# DroidOS.net
KiCad netlist of a schematic drawn in EAGLE
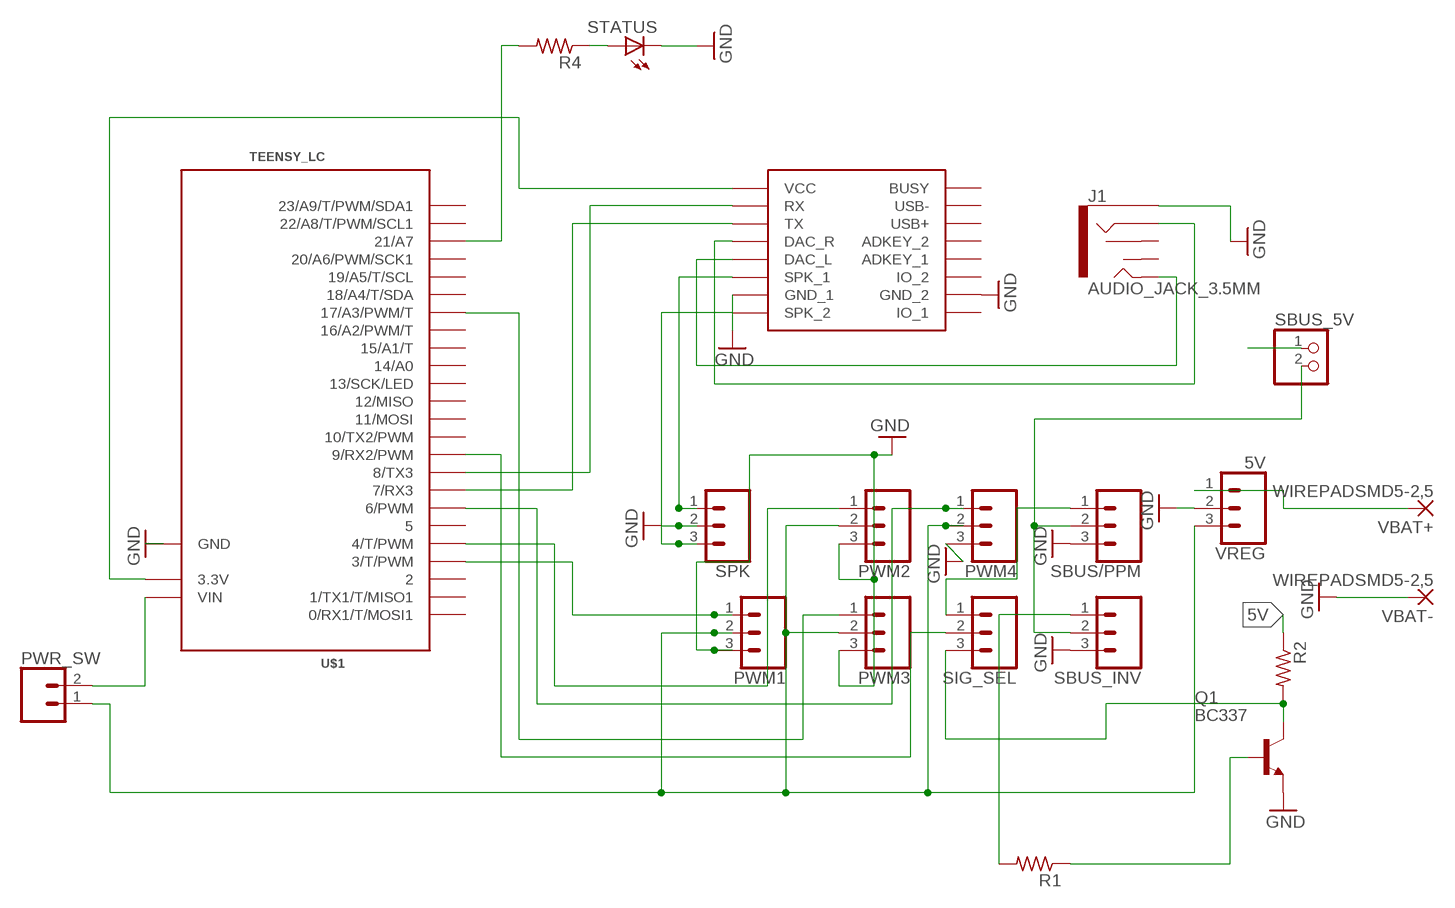
[diagram p0: schematic, sheet 1]

(export (version "E")
  (design (tool "Eeschema 10.0.6"))
  (components
    (comp (ref "J1")
      (value "AUDIO_JACK_3.5MM")
      (footprint "eagle-import:AUDIO-JACK-KIT")
      (libsource (lib "eagle-import") (part "AUDIO_JACK_3.5MM_KIT"))
    )
    (comp (ref "PWM1")
      (value "CONN_03")
      (footprint "eagle-import:1X03")
      (libsource (lib "eagle-import") (part "CONN_03"))
    )
    (comp (ref "PWM2")
      (value "CONN_03")
      (footprint "eagle-import:1X03")
      (libsource (lib "eagle-import") (part "CONN_03"))
    )
    (comp (ref "PWM3")
      (value "CONN_03")
      (footprint "eagle-import:1X03")
      (libsource (lib "eagle-import") (part "CONN_03"))
    )
    (comp (ref "PWM4")
      (value "CONN_03")
      (footprint "eagle-import:1X03")
      (libsource (lib "eagle-import") (part "CONN_03"))
    )
    (comp (ref "PWR_SW")
      (value "CONN_02")
      (footprint "eagle-import:1X02")
      (libsource (lib "eagle-import") (part "CONN_02"))
    )
    (comp (ref "Q1")
      (value "BC337")
      (footprint "eagle-import:TO92")
      (libsource (lib "eagle-import") (part "BC337"))
    )
    (comp (ref "R1")
      (value "R-US_R0805")
      (footprint "eagle-import:R0805")
      (libsource (lib "eagle-import") (part "R-US_R0805"))
    )
    (comp (ref "R2")
      (value "R-US_R0805")
      (footprint "eagle-import:R0805")
      (libsource (lib "eagle-import") (part "R-US_R0805"))
    )
    (comp (ref "R4")
      (value "R-US_R0805")
      (footprint "eagle-import:R0805")
      (libsource (lib "eagle-import") (part "R-US_R0805"))
    )
    (comp (ref "SBUS/PPM")
      (value "CONN_03")
      (footprint "eagle-import:1X03")
      (libsource (lib "eagle-import") (part "CONN_03"))
    )
    (comp (ref "SBUS_5V")
      (value "PINHD-1X2")
      (footprint "eagle-import:1X02")
      (libsource (lib "eagle-import") (part "PINHD-1X2"))
    )
    (comp (ref "SBUS_INV")
      (value "CONN_03")
      (footprint "eagle-import:1X03")
      (libsource (lib "eagle-import") (part "CONN_03"))
    )
    (comp (ref "SIG_SEL")
      (value "CONN_03")
      (footprint "eagle-import:1X03")
      (libsource (lib "eagle-import") (part "CONN_03"))
    )
    (comp (ref "SPK")
      (value "CONN_03")
      (footprint "eagle-import:1X03")
      (libsource (lib "eagle-import") (part "CONN_03"))
    )
    (comp (ref "STATUS")
      (value "LEDSML0805")
      (footprint "eagle-import:SML0805")
      (libsource (lib "eagle-import") (part "LEDSML0805"))
    )
    (comp (ref "U$1")
      (value "TEENSY_LC")
      (footprint "eagle-import:TEENSY_3.0-3.2&LC_DIL")
      (libsource (lib "eagle-import") (part "TEENSY_LC_DIL"))
    )
    (comp (ref "U$2")
      (value "DFPLAYER")
      (footprint "eagle-import:DFPLAYER")
      (libsource (lib "eagle-import") (part "DFPLAYER"))
    )
    (comp (ref "VBAT+")
      (value "WIREPADSMD5-2,5")
      (footprint "eagle-import:5-2,5")
      (libsource (lib "eagle-import") (part "WIREPADSMD5-2,5"))
    )
    (comp (ref "VBAT-")
      (value "WIREPADSMD5-2,5")
      (footprint "eagle-import:5-2,5")
      (libsource (lib "eagle-import") (part "WIREPADSMD5-2,5"))
    )
    (comp (ref "VREG")
      (value "5V")
      (footprint "eagle-import:1X03")
      (libsource (lib "eagle-import") (part "CONN_03"))
    )
  )
  (nets
    (net (code "1") (name "5V") (class "Default")
      (node (ref "PWM1") (pin "2") (pinfunction "2_2") (pintype "passive"))
      (node (ref "PWM2") (pin "2") (pinfunction "2_2") (pintype "passive"))
      (node (ref "PWM3") (pin "2") (pinfunction "2_2") (pintype "passive"))
      (node (ref "PWM4") (pin "2") (pinfunction "2_2") (pintype "passive"))
      (node (ref "PWR_SW") (pin "1") (pinfunction "1_1") (pintype "passive"))
      (node (ref "R2") (pin "1") (pinfunction "1_1") (pintype "passive"))
      (node (ref "SBUS_5V") (pin "1") (pinfunction "1_1") (pintype "passive"))
      (node (ref "VREG") (pin "3") (pinfunction "3_3") (pintype "passive"))
    )
    (net (code "2") (name "GND") (class "Default")
      (node (ref "J1") (pin "SLEEVE") (pinfunction "SLEEVE_SLEEVE") (pintype "bidirectional"))
      (node (ref "PWM1") (pin "3") (pinfunction "3_3") (pintype "passive"))
      (node (ref "PWM2") (pin "3") (pinfunction "3_3") (pintype "passive"))
      (node (ref "PWM3") (pin "3") (pinfunction "3_3") (pintype "passive"))
      (node (ref "PWM4") (pin "3") (pinfunction "3_3") (pintype "passive"))
      (node (ref "Q1") (pin "1") (pinfunction "E_1") (pintype "passive"))
      (node (ref "SBUS/PPM") (pin "3") (pinfunction "3_3") (pintype "passive"))
      (node (ref "SBUS_INV") (pin "3") (pinfunction "3_3") (pintype "passive"))
      (node (ref "SPK") (pin "2") (pinfunction "2_2") (pintype "passive"))
      (node (ref "STATUS") (pin "C") (pinfunction "C_C") (pintype "passive"))
      (node (ref "U$1") (pin "AGND") (pinfunction "GND_AGND") (pintype "power_in"))
      (node (ref "U$1") (pin "GND") (pinfunction "GND_GND") (pintype "power_in"))
      (node (ref "U$2") (pin "GND_1") (pinfunction "GND_1_GND_1") (pintype "bidirectional"))
      (node (ref "U$2") (pin "GND_2") (pinfunction "GND_2_GND_2") (pintype "bidirectional"))
      (node (ref "VBAT-") (pin "1") (pinfunction "P_1") (pintype "passive"))
      (node (ref "VREG") (pin "2") (pinfunction "2_2") (pintype "passive"))
    )
    (net (code "3") (name "Net-(J1-PadRING)") (class "Default")
      (node (ref "J1") (pin "RING") (pinfunction "RING_RING") (pintype "bidirectional"))
      (node (ref "U$2") (pin "DAC_R") (pinfunction "DAC_R_DAC_R") (pintype "bidirectional"))
    )
    (net (code "4") (name "Net-(J1-PadTIP)") (class "Default")
      (node (ref "J1") (pin "TIP") (pinfunction "TIP_TIP") (pintype "bidirectional"))
      (node (ref "U$2") (pin "DAC_L") (pinfunction "DAC_L_DAC_L") (pintype "bidirectional"))
    )
    (net (code "5") (name "Net-(PWR_SW-Pad2)") (class "Default")
      (node (ref "PWR_SW") (pin "2") (pinfunction "2_2") (pintype "passive"))
      (node (ref "U$1") (pin "VIN") (pinfunction "VIN_VIN") (pintype "power_in"))
    )
    (net (code "6") (name "Net-(Q1-B)") (class "Default")
      (node (ref "Q1") (pin "2") (pinfunction "B_2") (pintype "passive"))
      (node (ref "R1") (pin "1") (pinfunction "1_1") (pintype "passive"))
    )
    (net (code "7") (name "Net-(Q1-C)") (class "Default")
      (node (ref "Q1") (pin "3") (pinfunction "C_3") (pintype "passive"))
      (node (ref "R2") (pin "2") (pinfunction "2_2") (pintype "passive"))
      (node (ref "SIG_SEL") (pin "3") (pinfunction "3_3") (pintype "passive"))
    )
    (net (code "8") (name "Net-(R1-Pad2)") (class "Default")
      (node (ref "R1") (pin "2") (pinfunction "2_2") (pintype "passive"))
      (node (ref "SBUS_INV") (pin "1") (pinfunction "1_1") (pintype "passive"))
    )
    (net (code "9") (name "Net-(R4-Pad1)") (class "Default")
      (node (ref "R4") (pin "1") (pinfunction "1_1") (pintype "passive"))
      (node (ref "STATUS") (pin "A") (pinfunction "A_A") (pintype "passive"))
    )
    (net (code "10") (name "Net-(R4-Pad2)") (class "Default")
      (node (ref "R4") (pin "2") (pinfunction "2_2") (pintype "passive"))
      (node (ref "U$1") (pin "21/A7") (pinfunction "21/A7_21/A7") (pintype "bidirectional"))
    )
    (net (code "11") (name "Net-(SBUS/PPM-Pad1)") (class "Default")
      (node (ref "SBUS/PPM") (pin "1") (pinfunction "1_1") (pintype "passive"))
      (node (ref "SIG_SEL") (pin "1") (pinfunction "1_1") (pintype "passive"))
    )
    (net (code "12") (name "Net-(SBUS/PPM-Pad2)") (class "Default")
      (node (ref "SBUS/PPM") (pin "2") (pinfunction "2_2") (pintype "passive"))
      (node (ref "SBUS_5V") (pin "2") (pinfunction "2_2") (pintype "passive"))
      (node (ref "SBUS_INV") (pin "2") (pinfunction "2_2") (pintype "passive"))
    )
    (net (code "13") (name "Net-(U$1-3{slash}T{slash}PWM)") (class "Default")
      (node (ref "PWM1") (pin "1") (pinfunction "1_1") (pintype "passive"))
      (node (ref "U$1") (pin "3") (pinfunction "3/T/PWM_3") (pintype "bidirectional"))
    )
    (net (code "14") (name "Net-(U$1-4{slash}T{slash}PWM)") (class "Default")
      (node (ref "PWM2") (pin "1") (pinfunction "1_1") (pintype "passive"))
      (node (ref "U$1") (pin "4") (pinfunction "4/T/PWM_4") (pintype "bidirectional"))
    )
    (net (code "15") (name "Net-(U$1-6{slash}PWM)") (class "Default")
      (node (ref "PWM4") (pin "1") (pinfunction "1_1") (pintype "passive"))
      (node (ref "U$1") (pin "6") (pinfunction "6/PWM_6") (pintype "bidirectional"))
    )
    (net (code "16") (name "Net-(U$1-7{slash}RX3)") (class "Default")
      (node (ref "U$1") (pin "7") (pinfunction "7/RX3_7") (pintype "bidirectional"))
      (node (ref "U$2") (pin "TX") (pinfunction "TX_TX") (pintype "bidirectional"))
    )
    (net (code "17") (name "Net-(U$1-8{slash}TX3)") (class "Default")
      (node (ref "U$1") (pin "8") (pinfunction "8/TX3_8") (pintype "bidirectional"))
      (node (ref "U$2") (pin "RX") (pinfunction "RX_RX") (pintype "bidirectional"))
    )
    (net (code "18") (name "Net-(U$1-9{slash}RX2{slash}PWM)") (class "Default")
      (node (ref "SIG_SEL") (pin "2") (pinfunction "2_2") (pintype "passive"))
      (node (ref "U$1") (pin "9") (pinfunction "9/RX2/PWM_9") (pintype "bidirectional"))
    )
    (net (code "19") (name "Net-(U$1-17{slash}A3{slash}PWM{slash}T)") (class "Default")
      (node (ref "PWM3") (pin "1") (pinfunction "1_1") (pintype "passive"))
      (node (ref "U$1") (pin "17/A3") (pinfunction "17/A3/PWM/T_17/A3") (pintype "bidirectional"))
    )
    (net (code "20") (name "Net-(U$1-Pad3.3V)") (class "Default")
      (node (ref "U$1") (pin "3.3V") (pinfunction "3.3V_3.3V") (pintype "power_in"))
      (node (ref "U$2") (pin "VCC") (pinfunction "VCC_VCC") (pintype "bidirectional"))
    )
    (net (code "21") (name "Net-(U$2-SPK_1)") (class "Default")
      (node (ref "SPK") (pin "1") (pinfunction "1_1") (pintype "passive"))
      (node (ref "U$2") (pin "SPK1") (pinfunction "SPK_1_SPK1") (pintype "bidirectional"))
    )
    (net (code "22") (name "Net-(U$2-SPK_2)") (class "Default")
      (node (ref "SPK") (pin "3") (pinfunction "3_3") (pintype "passive"))
      (node (ref "U$2") (pin "SPK2") (pinfunction "SPK_2_SPK2") (pintype "bidirectional"))
    )
    (net (code "23") (name "Net-(VBAT+-P)") (class "Default")
      (node (ref "VBAT+") (pin "1") (pinfunction "P_1") (pintype "passive"))
      (node (ref "VREG") (pin "1") (pinfunction "1_1") (pintype "passive"))
    )
    (net (code "24") (name "unconnected-(J1-PadRSH)") (class "Default")
      (node (ref "J1") (pin "RSH") (pinfunction "RSH_RSH") (pintype "bidirectional"))
    )
    (net (code "25") (name "unconnected-(J1-PadTSH)") (class "Default")
      (node (ref "J1") (pin "TSH") (pinfunction "TSH_TSH") (pintype "bidirectional"))
    )
    (net (code "26") (name "unconnected-(U$1-0{slash}RX1{slash}T{slash}MOSI1-Pad0)") (class "Default")
      (node (ref "U$1") (pin "0") (pinfunction "0/RX1/T/MOSI1_0") (pintype "bidirectional"))
    )
    (net (code "27") (name "unconnected-(U$1-1{slash}TX1{slash}T{slash}MISO1-Pad1)") (class "Default")
      (node (ref "U$1") (pin "1") (pinfunction "1/TX1/T/MISO1_1") (pintype "bidirectional"))
    )
    (net (code "28") (name "unconnected-(U$1-10{slash}TX2{slash}PWM-Pad10)") (class "Default")
      (node (ref "U$1") (pin "10") (pinfunction "10/TX2/PWM_10") (pintype "bidirectional"))
    )
    (net (code "29") (name "unconnected-(U$1-11{slash}MOSI-Pad11)") (class "Default")
      (node (ref "U$1") (pin "11") (pinfunction "11/MOSI_11") (pintype "bidirectional"))
    )
    (net (code "30") (name "unconnected-(U$1-12{slash}MISO-Pad12)") (class "Default")
      (node (ref "U$1") (pin "12") (pinfunction "12/MISO_12") (pintype "bidirectional"))
    )
    (net (code "31") (name "unconnected-(U$1-13{slash}SCK{slash}LED-Pad13)") (class "Default")
      (node (ref "U$1") (pin "13") (pinfunction "13/SCK/LED_13") (pintype "bidirectional"))
    )
    (net (code "32") (name "unconnected-(U$1-15{slash}A1{slash}T-Pad15{slash}A1)") (class "Default")
      (node (ref "U$1") (pin "15/A1") (pinfunction "15/A1/T_15/A1") (pintype "bidirectional"))
    )
    (net (code "33") (name "unconnected-(U$1-16{slash}A2{slash}PWM{slash}T-Pad16{slash}A2)") (class "Default")
      (node (ref "U$1") (pin "16/A2") (pinfunction "16/A2/PWM/T_16/A2") (pintype "bidirectional"))
    )
    (net (code "34") (name "unconnected-(U$1-18{slash}A4{slash}T{slash}SDA-Pad18{slash}A4)") (class "Default")
      (node (ref "U$1") (pin "18/A4") (pinfunction "18/A4/T/SDA_18/A4") (pintype "bidirectional"))
    )
    (net (code "35") (name "unconnected-(U$1-19{slash}A5{slash}T{slash}SCL-Pad19{slash}A5)") (class "Default")
      (node (ref "U$1") (pin "19/A5") (pinfunction "19/A5/T/SCL_19/A5") (pintype "bidirectional"))
    )
    (net (code "36") (name "unconnected-(U$1-20{slash}A6{slash}PWM{slash}SCK1-Pad20{slash}A6)") (class "Default")
      (node (ref "U$1") (pin "20/A6") (pinfunction "20/A6/PWM/SCK1_20/A6") (pintype "bidirectional"))
    )
    (net (code "37") (name "unconnected-(U$1-22{slash}A8{slash}T{slash}PWM{slash}SCL1-Pad22{slash}A8)") (class "Default")
      (node (ref "U$1") (pin "22/A8") (pinfunction "22/A8/T/PWM/SCL1_22/A8") (pintype "bidirectional"))
    )
    (net (code "38") (name "unconnected-(U$1-23{slash}A9{slash}T{slash}PWM{slash}SDA1-Pad23{slash}A9)") (class "Default")
      (node (ref "U$1") (pin "23/A9") (pinfunction "23/A9/T/PWM/SDA1_23/A9") (pintype "bidirectional"))
    )
    (net (code "39") (name "unconnected-(U$1-Pad2)") (class "Default")
      (node (ref "U$1") (pin "2") (pinfunction "2_2") (pintype "bidirectional"))
    )
    (net (code "40") (name "unconnected-(U$1-Pad5)") (class "Default")
      (node (ref "U$1") (pin "5") (pinfunction "5_5") (pintype "bidirectional"))
    )
    (net (code "41") (name "unconnected-(U$1-Pad14{slash}A0)") (class "Default")
      (node (ref "U$1") (pin "14/A0") (pinfunction "14/A0_14/A0") (pintype "bidirectional"))
    )
    (net (code "42") (name "unconnected-(U$2-ADKEY_1-PadADKEY1)") (class "Default")
      (node (ref "U$2") (pin "ADKEY1") (pinfunction "ADKEY_1_ADKEY1") (pintype "bidirectional"))
    )
    (net (code "43") (name "unconnected-(U$2-ADKEY_2-PadADKEY2)") (class "Default")
      (node (ref "U$2") (pin "ADKEY2") (pinfunction "ADKEY_2_ADKEY2") (pintype "bidirectional"))
    )
    (net (code "44") (name "unconnected-(U$2-IO_1-PadIO1)") (class "Default")
      (node (ref "U$2") (pin "IO1") (pinfunction "IO_1_IO1") (pintype "bidirectional"))
    )
    (net (code "45") (name "unconnected-(U$2-IO_2-PadIO2)") (class "Default")
      (node (ref "U$2") (pin "IO2") (pinfunction "IO_2_IO2") (pintype "bidirectional"))
    )
    (net (code "46") (name "unconnected-(U$2-PadBUSY)") (class "Default")
      (node (ref "U$2") (pin "BUSY") (pinfunction "BUSY_BUSY") (pintype "bidirectional"))
    )
    (net (code "47") (name "unconnected-(U$2-PadUSB+)") (class "Default")
      (node (ref "U$2") (pin "USB+") (pinfunction "USB+_USB+") (pintype "bidirectional"))
    )
    (net (code "48") (name "unconnected-(U$2-PadUSB-)") (class "Default")
      (node (ref "U$2") (pin "USB-") (pinfunction "USB-_USB-") (pintype "bidirectional"))
    )
  )
)
